# Module_Current_Probe.net
KiCad netlist of a schematic drawn in EAGLE
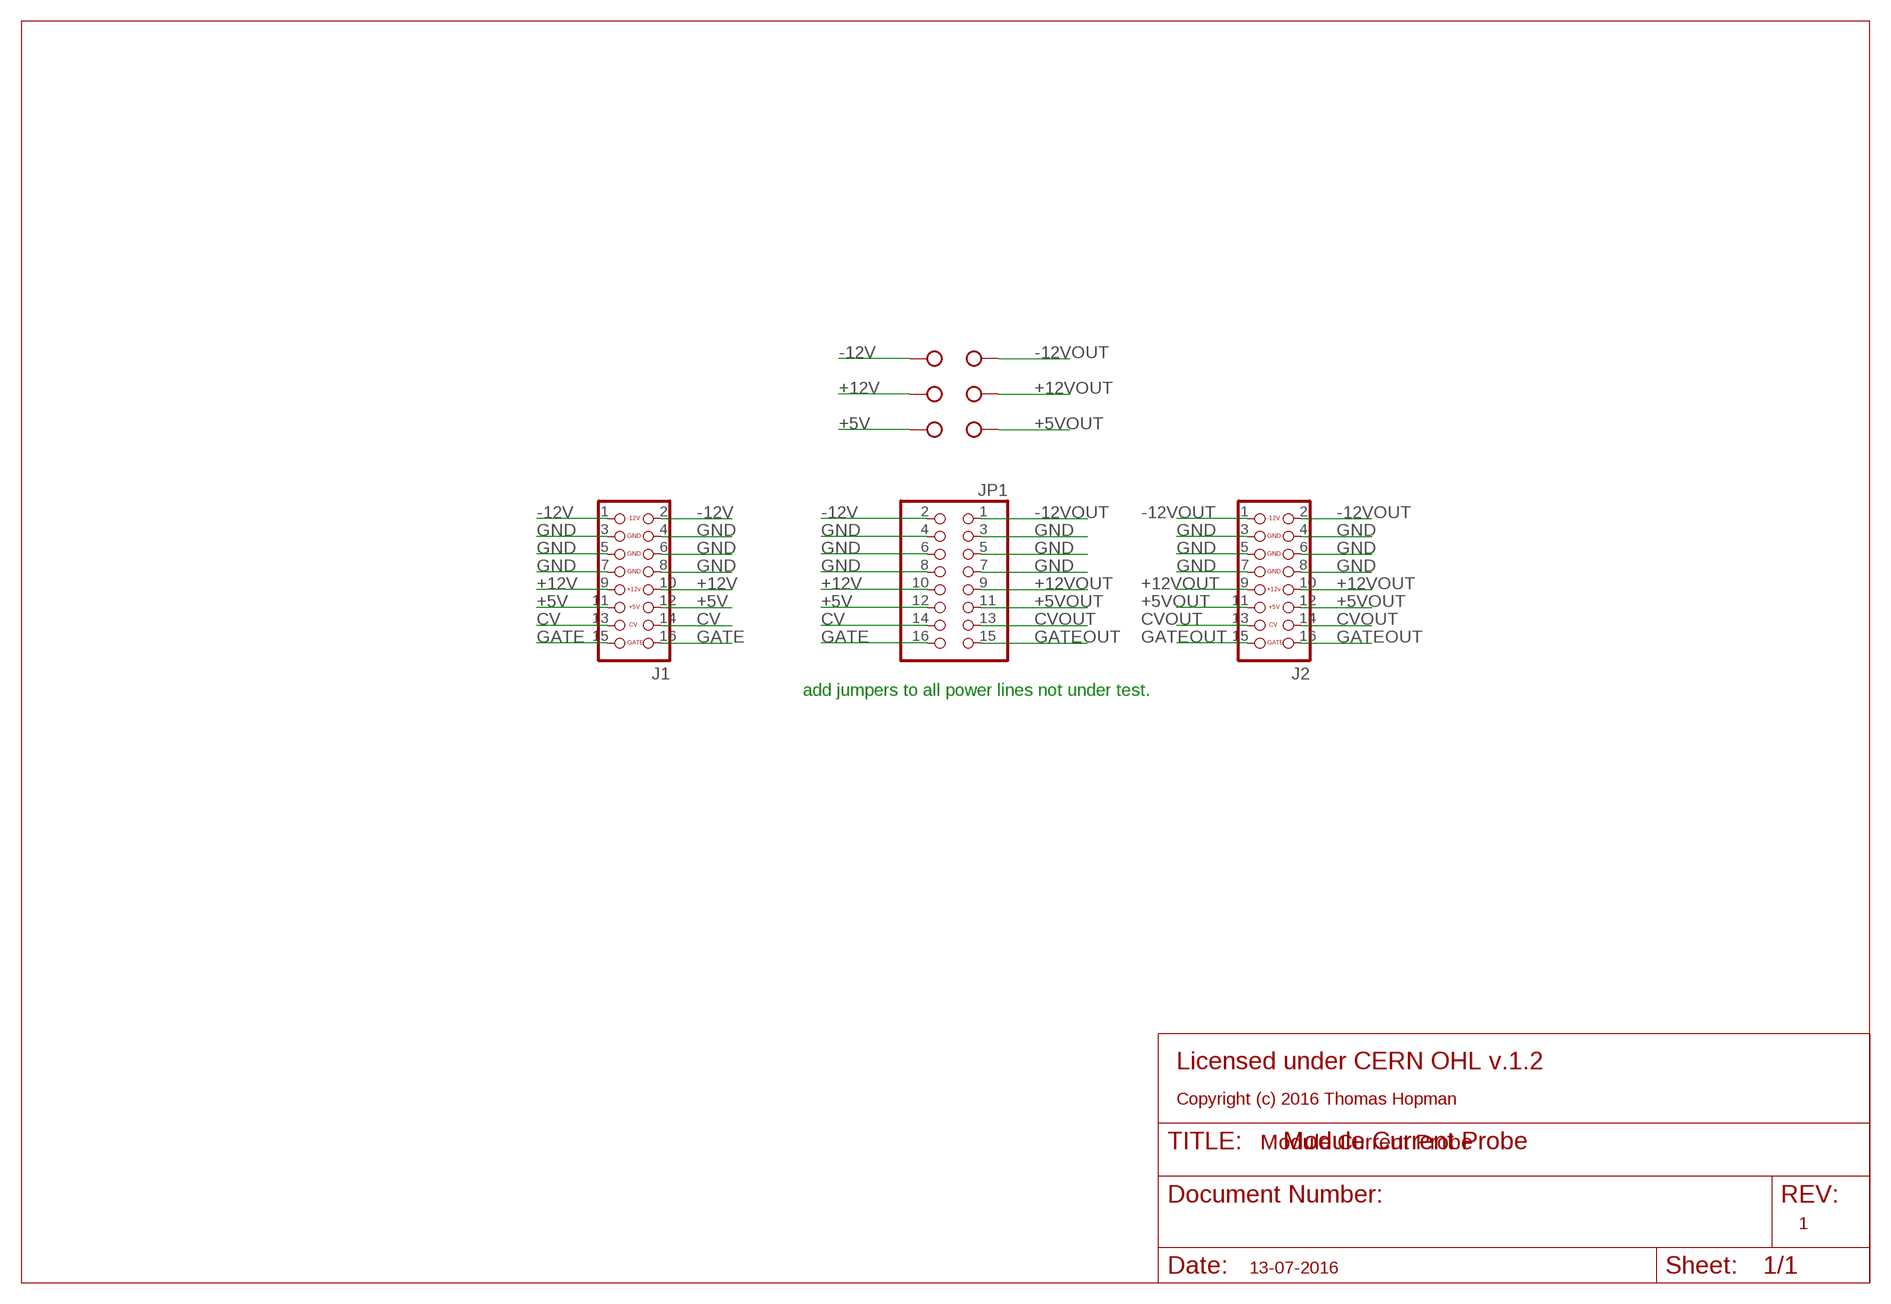
[diagram p0: schematic, sheet 1]

(export (version "E")
  (design (tool "Eeschema 10.0.6"))
  (components
    (comp (ref "J1")
      (value "CON_HEADER_2X08-PTH-SHROUDED")
      (footprint "eagle-import:PINSHRD_PTH_2X08")
      (libsource (lib "eagle-import") (part "CON_HEADER_2X08-PTH-SHROUDED"))
    )
    (comp (ref "J2")
      (value "CON_HEADER_2X08-PTH-SHROUDED")
      (footprint "eagle-import:PINSHRD_PTH_2X08")
      (libsource (lib "eagle-import") (part "CON_HEADER_2X08-PTH-SHROUDED"))
    )
    (comp (ref "J3")
      (value "BANANA-JACK")
      (footprint "eagle-import:BANANA-PRINT")
      (libsource (lib "eagle-import") (part "BANANA-JACK"))
    )
    (comp (ref "J4")
      (value "BANANA-JACK")
      (footprint "eagle-import:BANANA-PRINT")
      (libsource (lib "eagle-import") (part "BANANA-JACK"))
    )
    (comp (ref "J5")
      (value "BANANA-JACK")
      (footprint "eagle-import:BANANA-PRINT")
      (libsource (lib "eagle-import") (part "BANANA-JACK"))
    )
    (comp (ref "J6")
      (value "BANANA-JACK")
      (footprint "eagle-import:BANANA-PRINT")
      (libsource (lib "eagle-import") (part "BANANA-JACK"))
    )
    (comp (ref "J7")
      (value "BANANA-JACK")
      (footprint "eagle-import:BANANA-PRINT")
      (libsource (lib "eagle-import") (part "BANANA-JACK"))
    )
    (comp (ref "J8")
      (value "BANANA-JACK")
      (footprint "eagle-import:BANANA-PRINT")
      (libsource (lib "eagle-import") (part "BANANA-JACK"))
    )
    (comp (ref "JP1")
      (value "PINHD-2X8")
      (footprint "eagle-import:2X08")
      (libsource (lib "eagle-import") (part "PINHD-2X8"))
    )
  )
  (nets
    (net (code "1") (name "/+5V") (class "Default")
      (node (ref "J1") (pin "11") (pinfunction "11_11") (pintype "passive"))
      (node (ref "J1") (pin "12") (pinfunction "12_12") (pintype "passive"))
      (node (ref "J5") (pin "P$1") (pinfunction "PIN_P$1") (pintype "bidirectional"))
      (node (ref "JP1") (pin "12") (pinfunction "12_12") (pintype "passive"))
    )
    (net (code "2") (name "/+5VOUT") (class "Default")
      (node (ref "J2") (pin "11") (pinfunction "11_11") (pintype "passive"))
      (node (ref "J2") (pin "12") (pinfunction "12_12") (pintype "passive"))
      (node (ref "J8") (pin "P$1") (pinfunction "PIN_P$1") (pintype "bidirectional"))
      (node (ref "JP1") (pin "11") (pinfunction "11_11") (pintype "passive"))
    )
    (net (code "3") (name "/+12V") (class "Default")
      (node (ref "J1") (pin "10") (pinfunction "10_10") (pintype "passive"))
      (node (ref "J1") (pin "9") (pinfunction "9_9") (pintype "passive"))
      (node (ref "J4") (pin "P$1") (pinfunction "PIN_P$1") (pintype "bidirectional"))
      (node (ref "JP1") (pin "10") (pinfunction "10_10") (pintype "passive"))
    )
    (net (code "4") (name "/+12VOUT") (class "Default")
      (node (ref "J2") (pin "10") (pinfunction "10_10") (pintype "passive"))
      (node (ref "J2") (pin "9") (pinfunction "9_9") (pintype "passive"))
      (node (ref "J7") (pin "P$1") (pinfunction "PIN_P$1") (pintype "bidirectional"))
      (node (ref "JP1") (pin "9") (pinfunction "9_9") (pintype "passive"))
    )
    (net (code "5") (name "/-12V") (class "Default")
      (node (ref "J1") (pin "1") (pinfunction "1_1") (pintype "passive"))
      (node (ref "J1") (pin "2") (pinfunction "2_2") (pintype "passive"))
      (node (ref "J3") (pin "P$1") (pinfunction "PIN_P$1") (pintype "bidirectional"))
      (node (ref "JP1") (pin "2") (pinfunction "2_2") (pintype "passive"))
    )
    (net (code "6") (name "/-12VOUT") (class "Default")
      (node (ref "J2") (pin "1") (pinfunction "1_1") (pintype "passive"))
      (node (ref "J2") (pin "2") (pinfunction "2_2") (pintype "passive"))
      (node (ref "J6") (pin "P$1") (pinfunction "PIN_P$1") (pintype "bidirectional"))
      (node (ref "JP1") (pin "1") (pinfunction "1_1") (pintype "passive"))
    )
    (net (code "7") (name "/CV") (class "Default")
      (node (ref "J1") (pin "13") (pinfunction "13_13") (pintype "passive"))
      (node (ref "J1") (pin "14") (pinfunction "14_14") (pintype "passive"))
      (node (ref "JP1") (pin "14") (pinfunction "14_14") (pintype "passive"))
    )
    (net (code "8") (name "/CVOUT") (class "Default")
      (node (ref "J2") (pin "13") (pinfunction "13_13") (pintype "passive"))
      (node (ref "J2") (pin "14") (pinfunction "14_14") (pintype "passive"))
      (node (ref "JP1") (pin "13") (pinfunction "13_13") (pintype "passive"))
    )
    (net (code "9") (name "/GATE") (class "Default")
      (node (ref "J1") (pin "15") (pinfunction "15_15") (pintype "passive"))
      (node (ref "J1") (pin "16") (pinfunction "16_16") (pintype "passive"))
      (node (ref "JP1") (pin "16") (pinfunction "16_16") (pintype "passive"))
    )
    (net (code "10") (name "/GATEOUT") (class "Default")
      (node (ref "J2") (pin "15") (pinfunction "15_15") (pintype "passive"))
      (node (ref "J2") (pin "16") (pinfunction "16_16") (pintype "passive"))
      (node (ref "JP1") (pin "15") (pinfunction "15_15") (pintype "passive"))
    )
    (net (code "11") (name "/GND") (class "Default")
      (node (ref "J1") (pin "3") (pinfunction "3_3") (pintype "passive"))
      (node (ref "J1") (pin "4") (pinfunction "4_4") (pintype "passive"))
      (node (ref "J1") (pin "5") (pinfunction "5_5") (pintype "passive"))
      (node (ref "J1") (pin "6") (pinfunction "6_6") (pintype "passive"))
      (node (ref "J1") (pin "7") (pinfunction "7_7") (pintype "passive"))
      (node (ref "J1") (pin "8") (pinfunction "8_8") (pintype "passive"))
      (node (ref "J2") (pin "3") (pinfunction "3_3") (pintype "passive"))
      (node (ref "J2") (pin "4") (pinfunction "4_4") (pintype "passive"))
      (node (ref "J2") (pin "5") (pinfunction "5_5") (pintype "passive"))
      (node (ref "J2") (pin "6") (pinfunction "6_6") (pintype "passive"))
      (node (ref "J2") (pin "7") (pinfunction "7_7") (pintype "passive"))
      (node (ref "J2") (pin "8") (pinfunction "8_8") (pintype "passive"))
      (node (ref "JP1") (pin "3") (pinfunction "3_3") (pintype "passive"))
      (node (ref "JP1") (pin "4") (pinfunction "4_4") (pintype "passive"))
      (node (ref "JP1") (pin "5") (pinfunction "5_5") (pintype "passive"))
      (node (ref "JP1") (pin "6") (pinfunction "6_6") (pintype "passive"))
      (node (ref "JP1") (pin "7") (pinfunction "7_7") (pintype "passive"))
      (node (ref "JP1") (pin "8") (pinfunction "8_8") (pintype "passive"))
    )
  )
)
